# Project_MS4.net
KiCad netlist of a schematic drawn in EAGLE
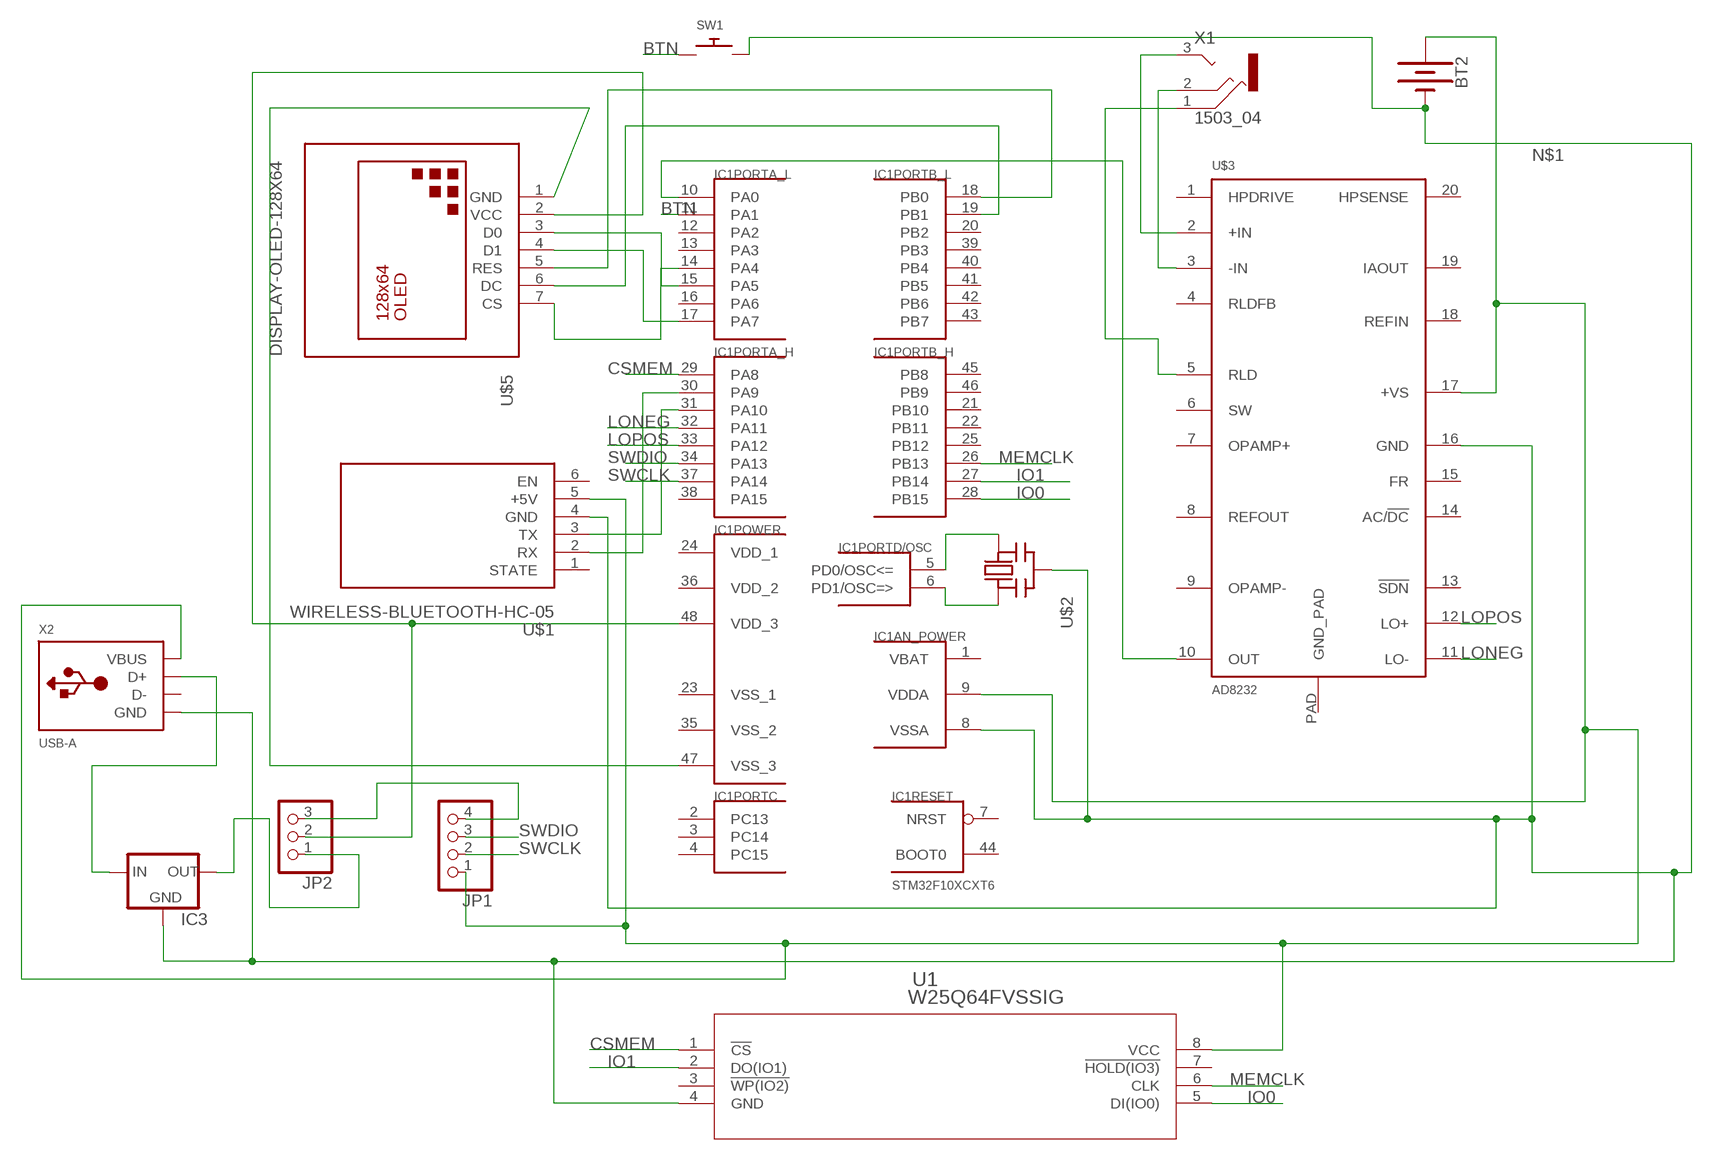
[diagram p0: schematic, sheet 1]

(export (version "E")
  (design (tool "Eeschema 10.0.6"))
  (components
    (comp (ref "BT2")
      (value "BATTERY-AAA_KIT")
      (footprint "eagle-import:BATTERY-AAA-KIT")
      (libsource (lib "eagle-import") (part "BATTERY-AAA_KIT"))
    )
    (comp (ref "IC1")
      (value "STM32F10XCXT6")
      (footprint "eagle-import:TQFP48")
      (libsource (lib "eagle-import") (part "STM32F10XCXT6"))
    )
    (comp (ref "IC3")
      (value "MCP1700INLINE")
      (footprint "eagle-import:TO92-INLINE")
      (libsource (lib "eagle-import") (part "MCP1700INLINE"))
    )
    (comp (ref "JP1")
      (value "PINHD-1X4")
      (footprint "eagle-import:1X04")
      (libsource (lib "eagle-import") (part "PINHD-1X4"))
    )
    (comp (ref "JP2")
      (value "PINHD-1X3")
      (footprint "eagle-import:1X03")
      (libsource (lib "eagle-import") (part "PINHD-1X3"))
    )
    (comp (ref "SW1")
      (value "SWITCH_PUSHBUTTONC&K_KSS")
      (footprint "eagle-import:BTN_CK_KSS")
      (libsource (lib "eagle-import") (part "SWITCH_PUSHBUTTONC&K_KSS"))
    )
    (comp (ref "U$1")
      (value "WIRELESS-BLUETOOTH-HC-05")
      (footprint "eagle-import:WIRELESS-BLUETOOTH-HC-05")
      (libsource (lib "eagle-import") (part "WIRELESS-BLUETOOTH-HC-05"))
    )
    (comp (ref "U$2")
      (value "CERMOSCILL-AWCSR")
      (footprint "eagle-import:AWCSR")
      (libsource (lib "eagle-import") (part "CERMOSCILL-AWCSR"))
    )
    (comp (ref "U$3")
      (value "AD8232")
      (footprint "eagle-import:LFCSP_20")
      (fields (field (name "MF") "Analog Devices"))
      (libsource (lib "eagle-import") (part "AD8232"))
    )
    (comp (ref "U$5")
      (value "DISPLAY-OLED-128X64")
      (footprint "eagle-import:DISPLAY-OLED-128X64")
      (libsource (lib "eagle-import") (part "DISPLAY-OLED-128X64"))
    )
    (comp (ref "U1")
      (value "W25Q64FVSSIG")
      (footprint "eagle-import:WIN_SS-8")
      (libsource (lib "eagle-import") (part "W25Q64FVSSIG"))
    )
    (comp (ref "X1")
      (value "1503_04")
      (footprint "eagle-import:1503_04")
      (libsource (lib "eagle-import") (part "1503_04"))
    )
    (comp (ref "X2")
      (value "USB-A")
      (footprint "eagle-import:MOLEX_480371000")
      (libsource (lib "eagle-import") (part "USB-A"))
    )
  )
  (nets
    (net (code "1") (name "/BTN") (class "Default")
      (node (ref "IC1") (pin "11") (pinfunction "PA1_11") (pintype "bidirectional"))
      (node (ref "SW1") (pin "P$1") (pinfunction "P$1_P$1") (pintype "passive"))
    )
    (net (code "2") (name "/CSMEM") (class "Default")
      (node (ref "IC1") (pin "29") (pinfunction "PA8_29") (pintype "bidirectional"))
      (node (ref "U1") (pin "1") (pinfunction "~{CS}_1") (pintype "input"))
    )
    (net (code "3") (name "/IO0") (class "Default")
      (node (ref "IC1") (pin "28") (pinfunction "PB15_28") (pintype "bidirectional"))
      (node (ref "U1") (pin "5") (pinfunction "DI(IO0)_5") (pintype "bidirectional"))
    )
    (net (code "4") (name "/IO1") (class "Default")
      (node (ref "IC1") (pin "27") (pinfunction "PB14_27") (pintype "bidirectional"))
      (node (ref "U1") (pin "2") (pinfunction "DO(IO1)_2") (pintype "bidirectional"))
    )
    (net (code "5") (name "/LONEG") (class "Default")
      (node (ref "IC1") (pin "32") (pinfunction "PA11_32") (pintype "bidirectional"))
      (node (ref "U$3") (pin "11") (pinfunction "LO-_11") (pintype "bidirectional"))
    )
    (net (code "6") (name "/LOPOS") (class "Default")
      (node (ref "IC1") (pin "33") (pinfunction "PA12_33") (pintype "bidirectional"))
      (node (ref "U$3") (pin "12") (pinfunction "LO+_12") (pintype "bidirectional"))
    )
    (net (code "7") (name "/MEMCLK") (class "Default")
      (node (ref "IC1") (pin "26") (pinfunction "PB13_26") (pintype "bidirectional"))
      (node (ref "U1") (pin "6") (pinfunction "CLK_6") (pintype "input"))
    )
    (net (code "8") (name "/N$1") (class "Default")
      (node (ref "BT2") (pin "PWR@1") (pinfunction "+_PWR@1") (pintype "power_in"))
      (node (ref "IC1") (pin "9") (pinfunction "VDDA_9") (pintype "power_in"))
      (node (ref "JP1") (pin "1") (pinfunction "1_1") (pintype "passive"))
      (node (ref "U$1") (pin "5") (pinfunction "+5V_5") (pintype "power_in"))
      (node (ref "U$3") (pin "17") (pinfunction "+VS_17") (pintype "bidirectional"))
      (node (ref "U1") (pin "8") (pinfunction "VCC_8") (pintype "power_in"))
      (node (ref "X2") (pin "1") (pinfunction "VBUS_1") (pintype "power_in"))
    )
    (net (code "9") (name "/SWCLK") (class "Default")
      (node (ref "IC1") (pin "37") (pinfunction "PA14_37") (pintype "bidirectional"))
      (node (ref "JP1") (pin "2") (pinfunction "2_2") (pintype "passive"))
    )
    (net (code "10") (name "/SWDIO") (class "Default")
      (node (ref "IC1") (pin "34") (pinfunction "PA13_34") (pintype "bidirectional"))
      (node (ref "JP1") (pin "3") (pinfunction "3_3") (pintype "passive"))
    )
    (net (code "11") (name "/VBAT") (class "Default")
      (node (ref "IC1") (pin "1") (pinfunction "VBAT_1") (pintype "power_in"))
    )
    (net (code "12") (name "/VDD_1") (class "Default")
      (node (ref "IC1") (pin "24") (pinfunction "VDD_1_24") (pintype "power_in"))
    )
    (net (code "13") (name "/VDD_2") (class "Default")
      (node (ref "IC1") (pin "36") (pinfunction "VDD_2_36") (pintype "power_in"))
    )
    (net (code "14") (name "/VSS_1") (class "Default")
      (node (ref "IC1") (pin "23") (pinfunction "VSS_1_23") (pintype "power_in"))
    )
    (net (code "15") (name "/VSS_2") (class "Default")
      (node (ref "IC1") (pin "35") (pinfunction "VSS_2_35") (pintype "power_in"))
    )
    (net (code "16") (name "Net-(BT2--)") (class "Default")
      (node (ref "BT2") (pin "GND@1") (pinfunction "-_GND@1") (pintype "power_in"))
      (node (ref "IC1") (pin "8") (pinfunction "VSSA_8") (pintype "power_in"))
      (node (ref "IC3") (pin "1") (pinfunction "GND_1") (pintype "input"))
      (node (ref "SW1") (pin "P$2") (pinfunction "P$2_P$2") (pintype "passive"))
      (node (ref "U$1") (pin "4") (pinfunction "GND_4") (pintype "power_in"))
      (node (ref "U$2") (pin "2") (pinfunction "GND_2") (pintype "bidirectional"))
      (node (ref "U$3") (pin "16") (pinfunction "GND_16") (pintype "bidirectional"))
      (node (ref "U1") (pin "4") (pinfunction "GND_4") (pintype "power_in"))
      (node (ref "X2") (pin "4") (pinfunction "GND_4") (pintype "power_in"))
    )
    (net (code "17") (name "Net-(IC1B-PA9)") (class "Default")
      (node (ref "IC1") (pin "30") (pinfunction "PA9_30") (pintype "bidirectional"))
      (node (ref "U$1") (pin "2") (pinfunction "RX_2") (pintype "bidirectional"))
    )
    (net (code "18") (name "Net-(IC1B-PA10)") (class "Default")
      (node (ref "IC1") (pin "31") (pinfunction "PA10_31") (pintype "bidirectional"))
      (node (ref "U$1") (pin "3") (pinfunction "TX_3") (pintype "bidirectional"))
    )
    (net (code "19") (name "Net-(IC1C-PA0)") (class "Default")
      (node (ref "IC1") (pin "10") (pinfunction "PA0_10") (pintype "bidirectional"))
      (node (ref "U$3") (pin "10") (pinfunction "OUT_10") (pintype "bidirectional"))
    )
    (net (code "20") (name "Net-(IC1C-PA4)") (class "Default")
      (node (ref "IC1") (pin "14") (pinfunction "PA4_14") (pintype "bidirectional"))
      (node (ref "U$5") (pin "7") (pinfunction "CS_7") (pintype "bidirectional"))
    )
    (net (code "21") (name "Net-(IC1C-PA5)") (class "Default")
      (node (ref "IC1") (pin "15") (pinfunction "PA5_15") (pintype "bidirectional"))
      (node (ref "U$5") (pin "3") (pinfunction "D0_3") (pintype "bidirectional"))
    )
    (net (code "22") (name "Net-(IC1C-PA7)") (class "Default")
      (node (ref "IC1") (pin "17") (pinfunction "PA7_17") (pintype "bidirectional"))
      (node (ref "U$5") (pin "4") (pinfunction "D1_4") (pintype "bidirectional"))
    )
    (net (code "23") (name "Net-(IC1E-PB0)") (class "Default")
      (node (ref "IC1") (pin "18") (pinfunction "PB0_18") (pintype "bidirectional"))
      (node (ref "U$5") (pin "5") (pinfunction "RES_5") (pintype "bidirectional"))
    )
    (net (code "24") (name "Net-(IC1E-PB1)") (class "Default")
      (node (ref "IC1") (pin "19") (pinfunction "PB1_19") (pintype "bidirectional"))
      (node (ref "U$5") (pin "6") (pinfunction "DC_6") (pintype "bidirectional"))
    )
    (net (code "25") (name "Net-(IC1G-PD0{slash}OSC<=)") (class "Default")
      (node (ref "IC1") (pin "5") (pinfunction "PD0/OSC<=_5") (pintype "bidirectional"))
      (node (ref "U$2") (pin "3") (pinfunction "OUT_3") (pintype "bidirectional"))
    )
    (net (code "26") (name "Net-(IC1G-PD1{slash}OSC=>)") (class "Default")
      (node (ref "IC1") (pin "6") (pinfunction "PD1/OSC=>_6") (pintype "bidirectional"))
      (node (ref "U$2") (pin "1") (pinfunction "IN_1") (pintype "bidirectional"))
    )
    (net (code "27") (name "Net-(IC1H-VDD_3)") (class "Default")
      (node (ref "IC1") (pin "48") (pinfunction "VDD_3_48") (pintype "power_in"))
      (node (ref "JP2") (pin "2") (pinfunction "2_2") (pintype "passive"))
      (node (ref "U$5") (pin "2") (pinfunction "VCC_2") (pintype "power_in"))
    )
    (net (code "28") (name "Net-(IC1H-VSS_3)") (class "Default")
      (node (ref "IC1") (pin "47") (pinfunction "VSS_3_47") (pintype "power_in"))
      (node (ref "U$5") (pin "1") (pinfunction "GND_1") (pintype "power_in"))
    )
    (net (code "29") (name "Net-(IC3-IN)") (class "Default")
      (node (ref "IC3") (pin "2") (pinfunction "IN_2") (pintype "input"))
      (node (ref "X2") (pin "3") (pinfunction "D+_3") (pintype "bidirectional"))
    )
    (net (code "30") (name "Net-(IC3-OUT)") (class "Default")
      (node (ref "IC3") (pin "3") (pinfunction "OUT_3") (pintype "passive"))
      (node (ref "JP2") (pin "1") (pinfunction "1_1") (pintype "passive"))
    )
    (net (code "31") (name "Net-(JP1-Pad4)") (class "Default")
      (node (ref "JP1") (pin "4") (pinfunction "4_4") (pintype "passive"))
      (node (ref "JP2") (pin "3") (pinfunction "3_3") (pintype "passive"))
    )
    (net (code "32") (name "Net-(U$3-+IN)") (class "Default")
      (node (ref "U$3") (pin "2") (pinfunction "+IN_2") (pintype "bidirectional"))
      (node (ref "X1") (pin "3") (pinfunction "2_3") (pintype "passive"))
    )
    (net (code "33") (name "Net-(U$3--IN)") (class "Default")
      (node (ref "U$3") (pin "3") (pinfunction "-IN_3") (pintype "bidirectional"))
      (node (ref "X1") (pin "2") (pinfunction "3_2") (pintype "passive"))
    )
    (net (code "34") (name "Net-(U$3-RLD)") (class "Default")
      (node (ref "U$3") (pin "5") (pinfunction "RLD_5") (pintype "bidirectional"))
      (node (ref "X1") (pin "1") (pinfunction "1_1") (pintype "passive"))
    )
    (net (code "35") (name "unconnected-(IC1B-PA15-Pad38)") (class "Default")
      (node (ref "IC1") (pin "38") (pinfunction "PA15_38") (pintype "bidirectional"))
    )
    (net (code "36") (name "unconnected-(IC1C-PA2-Pad12)") (class "Default")
      (node (ref "IC1") (pin "12") (pinfunction "PA2_12") (pintype "bidirectional"))
    )
    (net (code "37") (name "unconnected-(IC1C-PA3-Pad13)") (class "Default")
      (node (ref "IC1") (pin "13") (pinfunction "PA3_13") (pintype "bidirectional"))
    )
    (net (code "38") (name "unconnected-(IC1C-PA6-Pad16)") (class "Default")
      (node (ref "IC1") (pin "16") (pinfunction "PA6_16") (pintype "bidirectional"))
    )
    (net (code "39") (name "unconnected-(IC1D-PB8-Pad45)") (class "Default")
      (node (ref "IC1") (pin "45") (pinfunction "PB8_45") (pintype "bidirectional"))
    )
    (net (code "40") (name "unconnected-(IC1D-PB9-Pad46)") (class "Default")
      (node (ref "IC1") (pin "46") (pinfunction "PB9_46") (pintype "bidirectional"))
    )
    (net (code "41") (name "unconnected-(IC1D-PB10-Pad21)") (class "Default")
      (node (ref "IC1") (pin "21") (pinfunction "PB10_21") (pintype "bidirectional"))
    )
    (net (code "42") (name "unconnected-(IC1D-PB11-Pad22)") (class "Default")
      (node (ref "IC1") (pin "22") (pinfunction "PB11_22") (pintype "bidirectional"))
    )
    (net (code "43") (name "unconnected-(IC1D-PB12-Pad25)") (class "Default")
      (node (ref "IC1") (pin "25") (pinfunction "PB12_25") (pintype "bidirectional"))
    )
    (net (code "44") (name "unconnected-(IC1E-PB2-Pad20)") (class "Default")
      (node (ref "IC1") (pin "20") (pinfunction "PB2_20") (pintype "bidirectional"))
    )
    (net (code "45") (name "unconnected-(IC1E-PB3-Pad39)") (class "Default")
      (node (ref "IC1") (pin "39") (pinfunction "PB3_39") (pintype "bidirectional"))
    )
    (net (code "46") (name "unconnected-(IC1E-PB4-Pad40)") (class "Default")
      (node (ref "IC1") (pin "40") (pinfunction "PB4_40") (pintype "bidirectional"))
    )
    (net (code "47") (name "unconnected-(IC1E-PB5-Pad41)") (class "Default")
      (node (ref "IC1") (pin "41") (pinfunction "PB5_41") (pintype "bidirectional"))
    )
    (net (code "48") (name "unconnected-(IC1E-PB6-Pad42)") (class "Default")
      (node (ref "IC1") (pin "42") (pinfunction "PB6_42") (pintype "bidirectional"))
    )
    (net (code "49") (name "unconnected-(IC1E-PB7-Pad43)") (class "Default")
      (node (ref "IC1") (pin "43") (pinfunction "PB7_43") (pintype "bidirectional"))
    )
    (net (code "50") (name "unconnected-(IC1F-PC13-Pad2)") (class "Default")
      (node (ref "IC1") (pin "2") (pinfunction "PC13_2") (pintype "bidirectional"))
    )
    (net (code "51") (name "unconnected-(IC1F-PC14-Pad3)") (class "Default")
      (node (ref "IC1") (pin "3") (pinfunction "PC14_3") (pintype "bidirectional"))
    )
    (net (code "52") (name "unconnected-(IC1F-PC15-Pad4)") (class "Default")
      (node (ref "IC1") (pin "4") (pinfunction "PC15_4") (pintype "bidirectional"))
    )
    (net (code "53") (name "unconnected-(IC1I-BOOT0-Pad44)") (class "Default")
      (node (ref "IC1") (pin "44") (pinfunction "BOOT0_44") (pintype "input"))
    )
    (net (code "54") (name "unconnected-(IC1I-NRST-Pad7)") (class "Default")
      (node (ref "IC1") (pin "7") (pinfunction "NRST_7") (pintype "input"))
    )
    (net (code "55") (name "unconnected-(U$1-EN-Pad6)") (class "Default")
      (node (ref "U$1") (pin "6") (pinfunction "EN_6") (pintype "bidirectional"))
    )
    (net (code "56") (name "unconnected-(U$1-STATE-Pad1)") (class "Default")
      (node (ref "U$1") (pin "1") (pinfunction "STATE_1") (pintype "bidirectional"))
    )
    (net (code "57") (name "unconnected-(U$3-AC{slash}~{DC}-Pad14)") (class "Default")
      (node (ref "U$3") (pin "14") (pinfunction "AC/~{DC}_14") (pintype "bidirectional"))
    )
    (net (code "58") (name "unconnected-(U$3-FR-Pad15)") (class "Default")
      (node (ref "U$3") (pin "15") (pinfunction "FR_15") (pintype "bidirectional"))
    )
    (net (code "59") (name "unconnected-(U$3-GND_PAD-PadPAD)") (class "Default")
      (node (ref "U$3") (pin "PAD") (pinfunction "GND_PAD_PAD") (pintype "bidirectional"))
    )
    (net (code "60") (name "unconnected-(U$3-HPDRIVE-Pad1)") (class "Default")
      (node (ref "U$3") (pin "1") (pinfunction "HPDRIVE_1") (pintype "bidirectional"))
    )
    (net (code "61") (name "unconnected-(U$3-HPSENSE-Pad20)") (class "Default")
      (node (ref "U$3") (pin "20") (pinfunction "HPSENSE_20") (pintype "bidirectional"))
    )
    (net (code "62") (name "unconnected-(U$3-IAOUT-Pad19)") (class "Default")
      (node (ref "U$3") (pin "19") (pinfunction "IAOUT_19") (pintype "bidirectional"))
    )
    (net (code "63") (name "unconnected-(U$3-OPAMP+-Pad7)") (class "Default")
      (node (ref "U$3") (pin "7") (pinfunction "OPAMP+_7") (pintype "bidirectional"))
    )
    (net (code "64") (name "unconnected-(U$3-OPAMP--Pad9)") (class "Default")
      (node (ref "U$3") (pin "9") (pinfunction "OPAMP-_9") (pintype "bidirectional"))
    )
    (net (code "65") (name "unconnected-(U$3-REFIN-Pad18)") (class "Default")
      (node (ref "U$3") (pin "18") (pinfunction "REFIN_18") (pintype "bidirectional"))
    )
    (net (code "66") (name "unconnected-(U$3-REFOUT-Pad8)") (class "Default")
      (node (ref "U$3") (pin "8") (pinfunction "REFOUT_8") (pintype "bidirectional"))
    )
    (net (code "67") (name "unconnected-(U$3-RLDFB-Pad4)") (class "Default")
      (node (ref "U$3") (pin "4") (pinfunction "RLDFB_4") (pintype "bidirectional"))
    )
    (net (code "68") (name "unconnected-(U$3-SW-Pad6)") (class "Default")
      (node (ref "U$3") (pin "6") (pinfunction "SW_6") (pintype "bidirectional"))
    )
    (net (code "69") (name "unconnected-(U$3-~{SDN}-Pad13)") (class "Default")
      (node (ref "U$3") (pin "13") (pinfunction "~{SDN}_13") (pintype "bidirectional"))
    )
    (net (code "70") (name "unconnected-(U1-~{HOLD(IO3})-Pad7)") (class "Default")
      (node (ref "U1") (pin "7") (pinfunction "~{HOLD(IO3})_7") (pintype "bidirectional"))
    )
    (net (code "71") (name "unconnected-(U1-~{WP(IO2})-Pad3)") (class "Default")
      (node (ref "U1") (pin "3") (pinfunction "~{WP(IO2})_3") (pintype "bidirectional"))
    )
    (net (code "72") (name "unconnected-(X2-D--Pad2)") (class "Default")
      (node (ref "X2") (pin "2") (pinfunction "D-_2") (pintype "bidirectional"))
    )
  )
)
